# schematic.net
KiCad netlist of a schematic drawn in EasyEDA
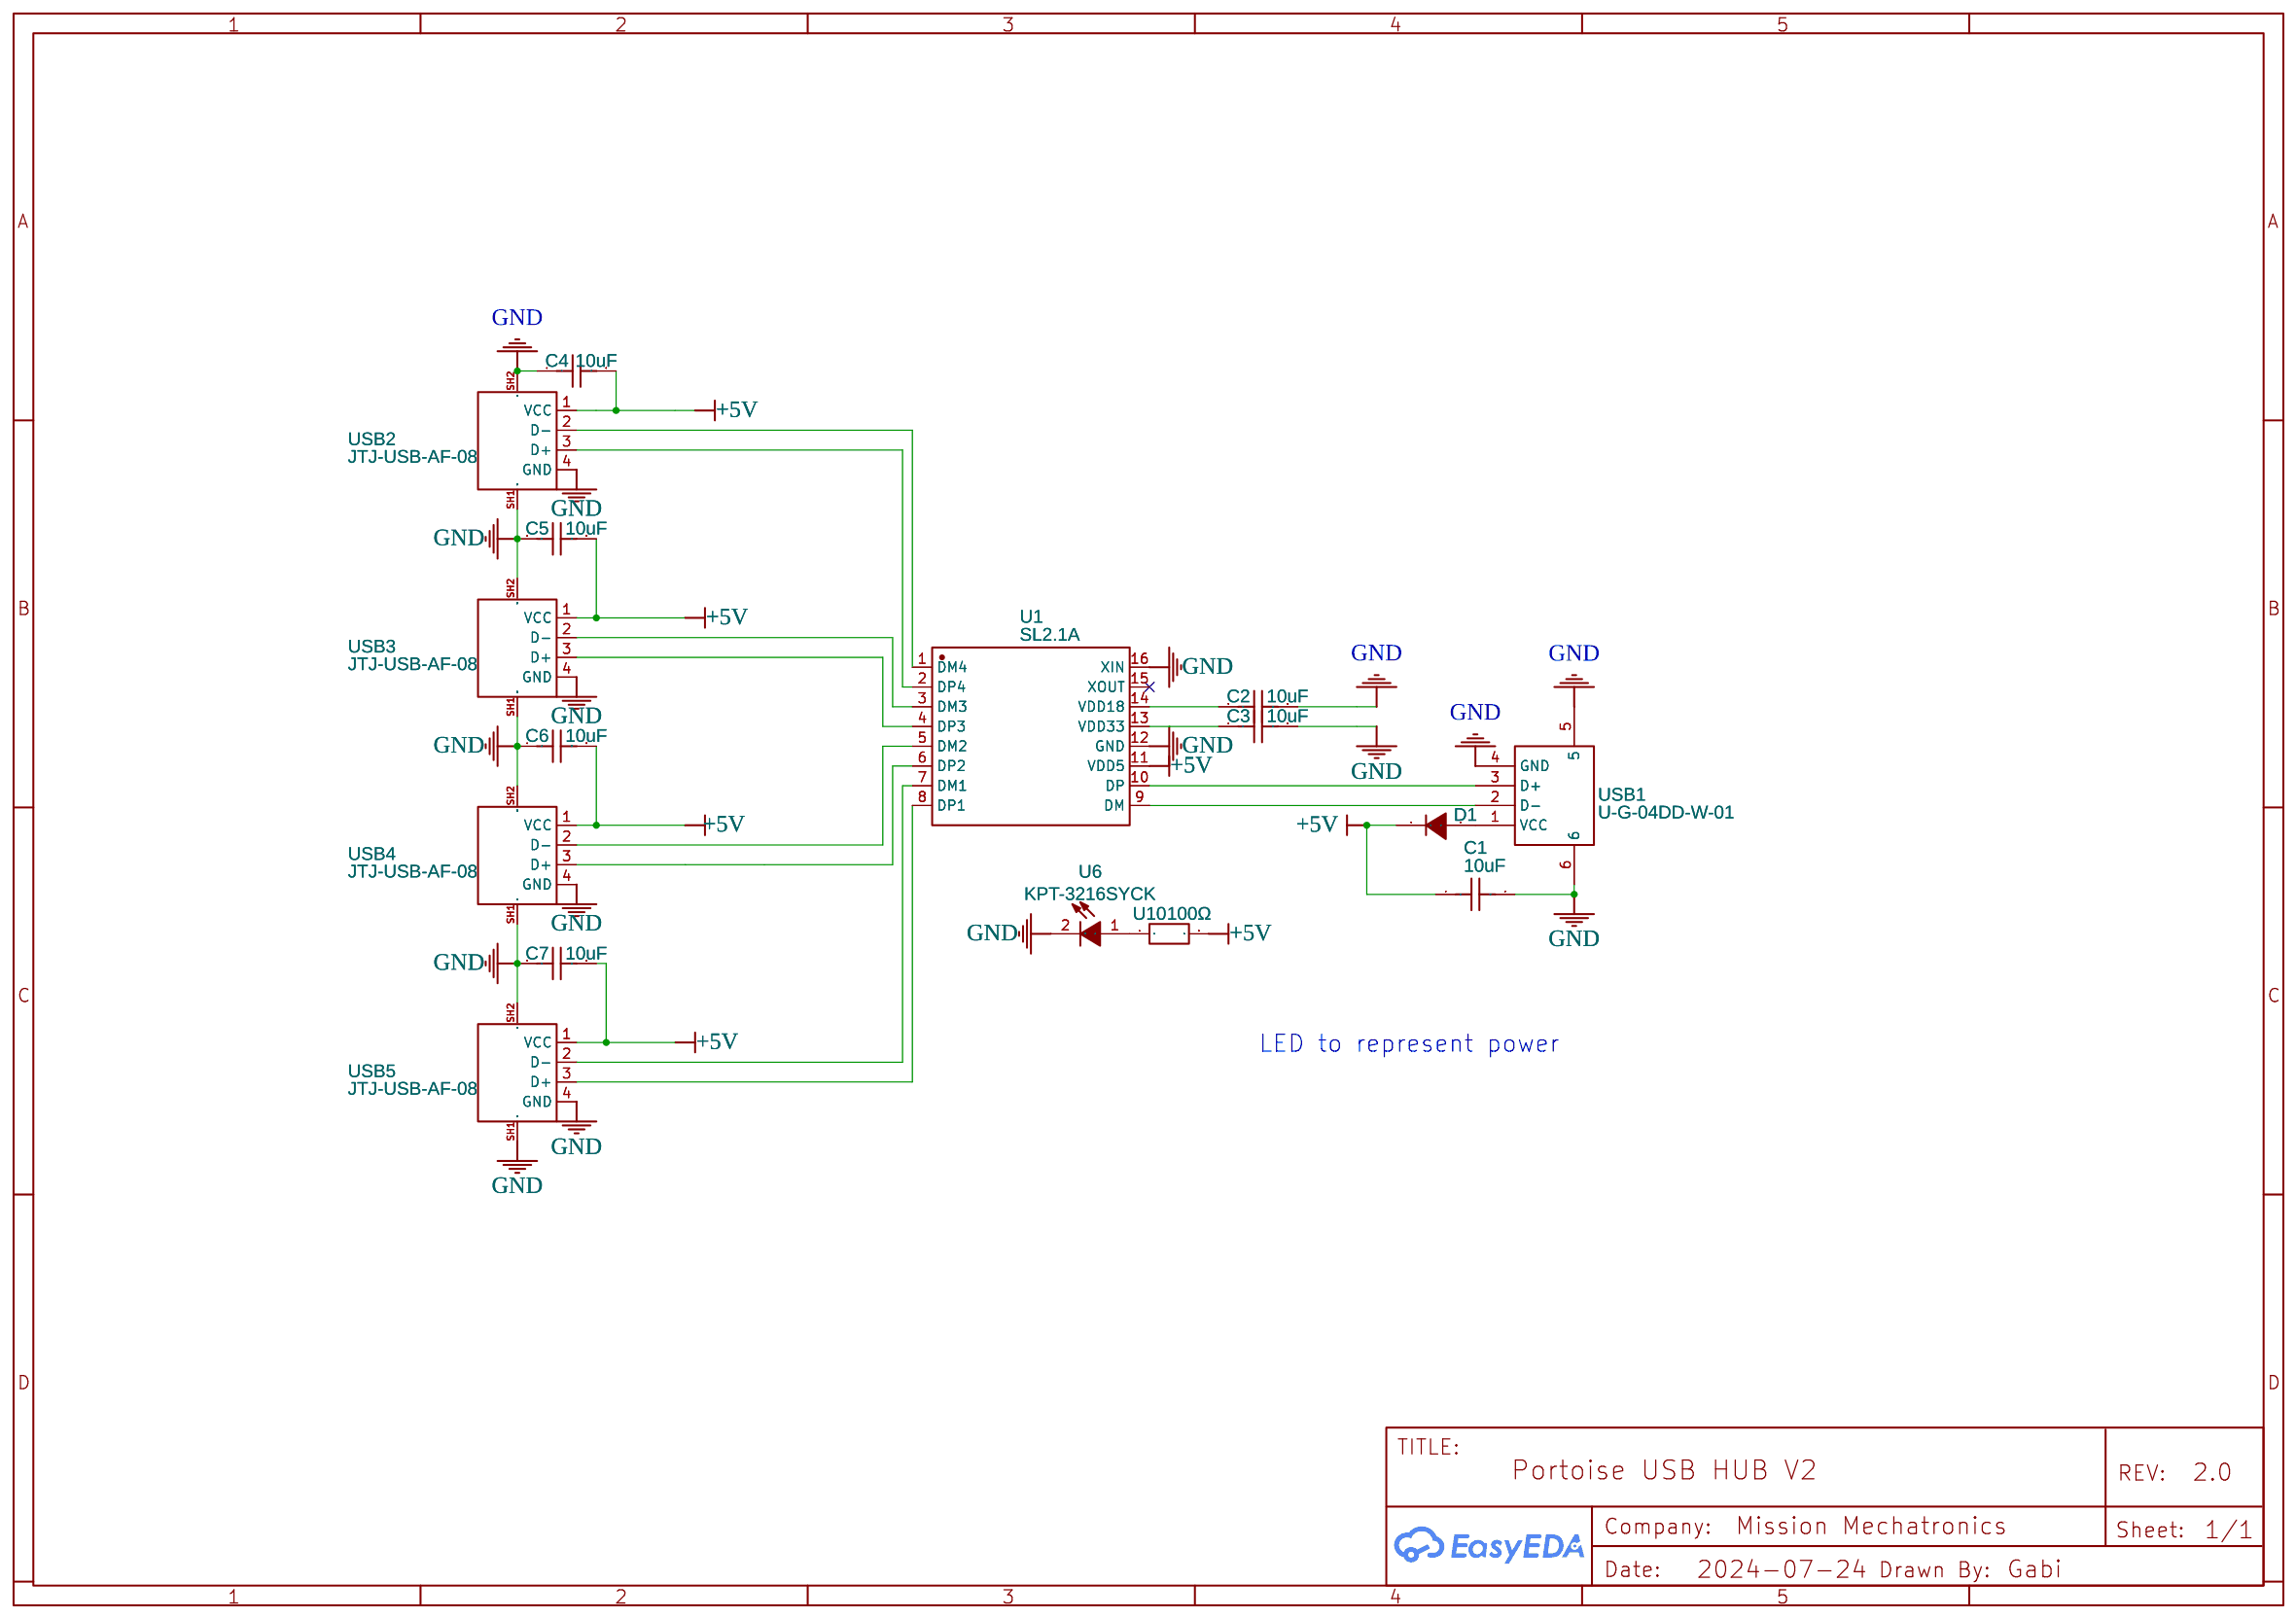
[diagram p0: schematic sheet]

(export (version "E")
  (design (tool "Eeschema 10.0.6"))
  (components
    (comp (ref "C1")
      (value "10uF")
      (fields
        (field (name "Manufacturer Part") "CL10A106KP8NNNC")
        (field (name "Manufacturer") "SAMSUNG(三星)")
      )
      (libsource (lib "") (part "CL10A106KP8NNNC"))
    )
    (comp (ref "C2")
      (value "10uF")
      (fields
        (field (name "Manufacturer Part") "CL10A106KP8NNNC")
        (field (name "Manufacturer") "SAMSUNG(三星)")
      )
      (libsource (lib "") (part "CL10A106KP8NNNC"))
    )
    (comp (ref "C3")
      (value "10uF")
      (fields
        (field (name "Manufacturer Part") "CL10A106KP8NNNC")
        (field (name "Manufacturer") "SAMSUNG(三星)")
      )
      (libsource (lib "") (part "CL10A106KP8NNNC"))
    )
    (comp (ref "C4")
      (value "10uF")
      (fields
        (field (name "Manufacturer Part") "CL10A106KP8NNNC")
        (field (name "Manufacturer") "SAMSUNG(三星)")
      )
      (libsource (lib "") (part "CL10A106KP8NNNC"))
    )
    (comp (ref "C5")
      (value "10uF")
      (fields
        (field (name "Manufacturer Part") "CL10A106KP8NNNC")
        (field (name "Manufacturer") "SAMSUNG(三星)")
      )
      (libsource (lib "") (part "CL10A106KP8NNNC"))
    )
    (comp (ref "C6")
      (value "10uF")
      (fields
        (field (name "Manufacturer Part") "CL10A106KP8NNNC")
        (field (name "Manufacturer") "SAMSUNG(三星)")
      )
      (libsource (lib "") (part "CL10A106KP8NNNC"))
    )
    (comp (ref "C7")
      (value "10uF")
      (fields
        (field (name "Manufacturer Part") "CL10A106KP8NNNC")
        (field (name "Manufacturer") "SAMSUNG(三星)")
      )
      (libsource (lib "") (part "CL10A106KP8NNNC"))
    )
    (comp (ref "D1")
      (value "NSR0320MW2T1G")
      (fields (field (name "Manufacturer") "onsemi(安森美)"))
      (libsource (lib "") (part "NSR0320MW2T1G"))
    )
    (comp (ref "U1")
      (value "SL2.1A")
      (fields (field (name "Manufacturer") "CoreChips(和芯润德)"))
      (libsource (lib "") (part "SL2.1A"))
    )
    (comp (ref "U6")
      (value "KPT-3216SYCK")
      (fields (field (name "Manufacturer") "Kingbright"))
      (libsource (lib "") (part "KPT-3216SYCK"))
    )
    (comp (ref "U10")
      (value "100Ω")
      (fields (field (name "Manufacturer Part") "OX101KE") (field (name "Manufacturer") "Ohmite"))
      (libsource (lib "") (part "OX101KE"))
    )
    (comp (ref "USB1")
      (value "U-G-04DD-W-01")
      (fields (field (name "Manufacturer Part") "U-G-O4DD-W-1") (field (name "Manufacturer") "韩国韩荣"))
      (libsource (lib "") (part "U-G-04DD-W-01"))
    )
    (comp (ref "USB2")
      (value "JTJ-USB-AF-08")
      (fields (field (name "Manufacturer Part") "902-131A1011D10100") (field (name "Manufacturer") "精拓金"))
      (libsource (lib "") (part "JTJ-USB-AF-08"))
    )
    (comp (ref "USB3")
      (value "JTJ-USB-AF-08")
      (fields (field (name "Manufacturer Part") "902-131A1011D10100") (field (name "Manufacturer") "精拓金"))
      (libsource (lib "") (part "JTJ-USB-AF-08"))
    )
    (comp (ref "USB4")
      (value "JTJ-USB-AF-08")
      (fields (field (name "Manufacturer Part") "902-131A1011D10100") (field (name "Manufacturer") "精拓金"))
      (libsource (lib "") (part "JTJ-USB-AF-08"))
    )
    (comp (ref "USB5")
      (value "JTJ-USB-AF-08")
      (fields (field (name "Manufacturer Part") "902-131A1011D10100") (field (name "Manufacturer") "精拓金"))
      (libsource (lib "") (part "JTJ-USB-AF-08"))
    )
  )
  (nets
    (net (code "1") (name "+5V") (class "Default")
      (node (ref "C1") (pin "1") (pinfunction "1_1") (pintype "unspecified"))
      (node (ref "C4") (pin "2") (pinfunction "2_2") (pintype "unspecified"))
      (node (ref "C5") (pin "2") (pinfunction "2_2") (pintype "unspecified"))
      (node (ref "C6") (pin "2") (pinfunction "2_2") (pintype "unspecified"))
      (node (ref "C7") (pin "2") (pinfunction "2_2") (pintype "unspecified"))
      (node (ref "D1") (pin "1") (pinfunction "C_1") (pintype "unspecified"))
      (node (ref "U1") (pin "11") (pinfunction "VDD5_11") (pintype "unspecified"))
      (node (ref "U10") (pin "2") (pinfunction "2_2") (pintype "unspecified"))
      (node (ref "USB2") (pin "1") (pinfunction "VCC_1") (pintype "input"))
      (node (ref "USB3") (pin "1") (pinfunction "VCC_1") (pintype "input"))
      (node (ref "USB4") (pin "1") (pinfunction "VCC_1") (pintype "input"))
      (node (ref "USB5") (pin "1") (pinfunction "VCC_1") (pintype "input"))
    )
    (net (code "2") (name "GND") (class "Default")
      (node (ref "C1") (pin "2") (pinfunction "2_2") (pintype "unspecified"))
      (node (ref "C2") (pin "2") (pinfunction "2_2") (pintype "unspecified"))
      (node (ref "C3") (pin "2") (pinfunction "2_2") (pintype "unspecified"))
      (node (ref "C4") (pin "1") (pinfunction "1_1") (pintype "unspecified"))
      (node (ref "C5") (pin "1") (pinfunction "1_1") (pintype "unspecified"))
      (node (ref "C6") (pin "1") (pinfunction "1_1") (pintype "unspecified"))
      (node (ref "C7") (pin "1") (pinfunction "1_1") (pintype "unspecified"))
      (node (ref "U1") (pin "12") (pinfunction "GND_12") (pintype "unspecified"))
      (node (ref "U1") (pin "16") (pinfunction "XIN_16") (pintype "unspecified"))
      (node (ref "U6") (pin "2") (pinfunction "C_2") (pintype "input"))
      (node (ref "USB1") (pin "4") (pinfunction "GND_4") (pintype "unspecified"))
      (node (ref "USB1") (pin "5") (pinfunction "5_5") (pintype "unspecified"))
      (node (ref "USB1") (pin "6") (pinfunction "6_6") (pintype "unspecified"))
      (node (ref "USB2") (pin "4") (pinfunction "GND_4") (pintype "input"))
      (node (ref "USB2") (pin "SH1") (pinfunction "SH1_SH1") (pintype "unspecified"))
      (node (ref "USB2") (pin "SH2") (pinfunction "SH2_SH2") (pintype "unspecified"))
      (node (ref "USB3") (pin "4") (pinfunction "GND_4") (pintype "input"))
      (node (ref "USB3") (pin "SH1") (pinfunction "SH1_SH1") (pintype "unspecified"))
      (node (ref "USB3") (pin "SH2") (pinfunction "SH2_SH2") (pintype "unspecified"))
      (node (ref "USB4") (pin "4") (pinfunction "GND_4") (pintype "input"))
      (node (ref "USB4") (pin "SH1") (pinfunction "SH1_SH1") (pintype "unspecified"))
      (node (ref "USB4") (pin "SH2") (pinfunction "SH2_SH2") (pintype "unspecified"))
      (node (ref "USB5") (pin "4") (pinfunction "GND_4") (pintype "input"))
      (node (ref "USB5") (pin "SH1") (pinfunction "SH1_SH1") (pintype "unspecified"))
      (node (ref "USB5") (pin "SH2") (pinfunction "SH2_SH2") (pintype "unspecified"))
    )
    (net (code "3") (name "Net-(D1-A)") (class "Default")
      (node (ref "D1") (pin "2") (pinfunction "A_2") (pintype "unspecified"))
      (node (ref "USB1") (pin "1") (pinfunction "VCC_1") (pintype "unspecified"))
    )
    (net (code "4") (name "Net-(U1-DM)") (class "Default")
      (node (ref "U1") (pin "9") (pinfunction "DM_9") (pintype "unspecified"))
      (node (ref "USB1") (pin "2") (pinfunction "D-_2") (pintype "unspecified"))
    )
    (net (code "5") (name "Net-(U1-DM1)") (class "Default")
      (node (ref "U1") (pin "7") (pinfunction "DM1_7") (pintype "unspecified"))
      (node (ref "USB5") (pin "2") (pinfunction "D-_2") (pintype "input"))
    )
    (net (code "6") (name "Net-(U1-DM2)") (class "Default")
      (node (ref "U1") (pin "5") (pinfunction "DM2_5") (pintype "unspecified"))
      (node (ref "USB4") (pin "2") (pinfunction "D-_2") (pintype "input"))
    )
    (net (code "7") (name "Net-(U1-DM3)") (class "Default")
      (node (ref "U1") (pin "3") (pinfunction "DM3_3") (pintype "unspecified"))
      (node (ref "USB3") (pin "2") (pinfunction "D-_2") (pintype "input"))
    )
    (net (code "8") (name "Net-(U1-DM4)") (class "Default")
      (node (ref "U1") (pin "1") (pinfunction "DM4_1") (pintype "unspecified"))
      (node (ref "USB2") (pin "2") (pinfunction "D-_2") (pintype "input"))
    )
    (net (code "9") (name "Net-(U1-DP)") (class "Default")
      (node (ref "U1") (pin "10") (pinfunction "DP_10") (pintype "unspecified"))
      (node (ref "USB1") (pin "3") (pinfunction "D+_3") (pintype "unspecified"))
    )
    (net (code "10") (name "Net-(U1-DP1)") (class "Default")
      (node (ref "U1") (pin "8") (pinfunction "DP1_8") (pintype "unspecified"))
      (node (ref "USB5") (pin "3") (pinfunction "D+_3") (pintype "input"))
    )
    (net (code "11") (name "Net-(U1-DP2)") (class "Default")
      (node (ref "U1") (pin "6") (pinfunction "DP2_6") (pintype "unspecified"))
      (node (ref "USB4") (pin "3") (pinfunction "D+_3") (pintype "input"))
    )
    (net (code "12") (name "Net-(U1-DP3)") (class "Default")
      (node (ref "U1") (pin "4") (pinfunction "DP3_4") (pintype "unspecified"))
      (node (ref "USB3") (pin "3") (pinfunction "D+_3") (pintype "input"))
    )
    (net (code "13") (name "Net-(U1-DP4)") (class "Default")
      (node (ref "U1") (pin "2") (pinfunction "DP4_2") (pintype "unspecified"))
      (node (ref "USB2") (pin "3") (pinfunction "D+_3") (pintype "input"))
    )
    (net (code "14") (name "Net-(U1-VDD18)") (class "Default")
      (node (ref "C2") (pin "1") (pinfunction "1_1") (pintype "unspecified"))
      (node (ref "U1") (pin "14") (pinfunction "VDD18_14") (pintype "unspecified"))
    )
    (net (code "15") (name "Net-(U1-VDD33)") (class "Default")
      (node (ref "C3") (pin "1") (pinfunction "1_1") (pintype "unspecified"))
      (node (ref "U1") (pin "13") (pinfunction "VDD33_13") (pintype "unspecified"))
    )
    (net (code "16") (name "Net-(U6-A)") (class "Default")
      (node (ref "U10") (pin "1") (pinfunction "1_1") (pintype "unspecified"))
      (node (ref "U6") (pin "1") (pinfunction "A_1") (pintype "input"))
    )
    (net (code "17") (name "unconnected-(U1-XOUT-Pad15)") (class "Default")
      (node (ref "U1") (pin "15") (pinfunction "XOUT_15") (pintype "unspecified+no_connect"))
    )
  )
)
